# MotionBoard_Rev_B.net
KiCad netlist of a schematic drawn in EAGLE
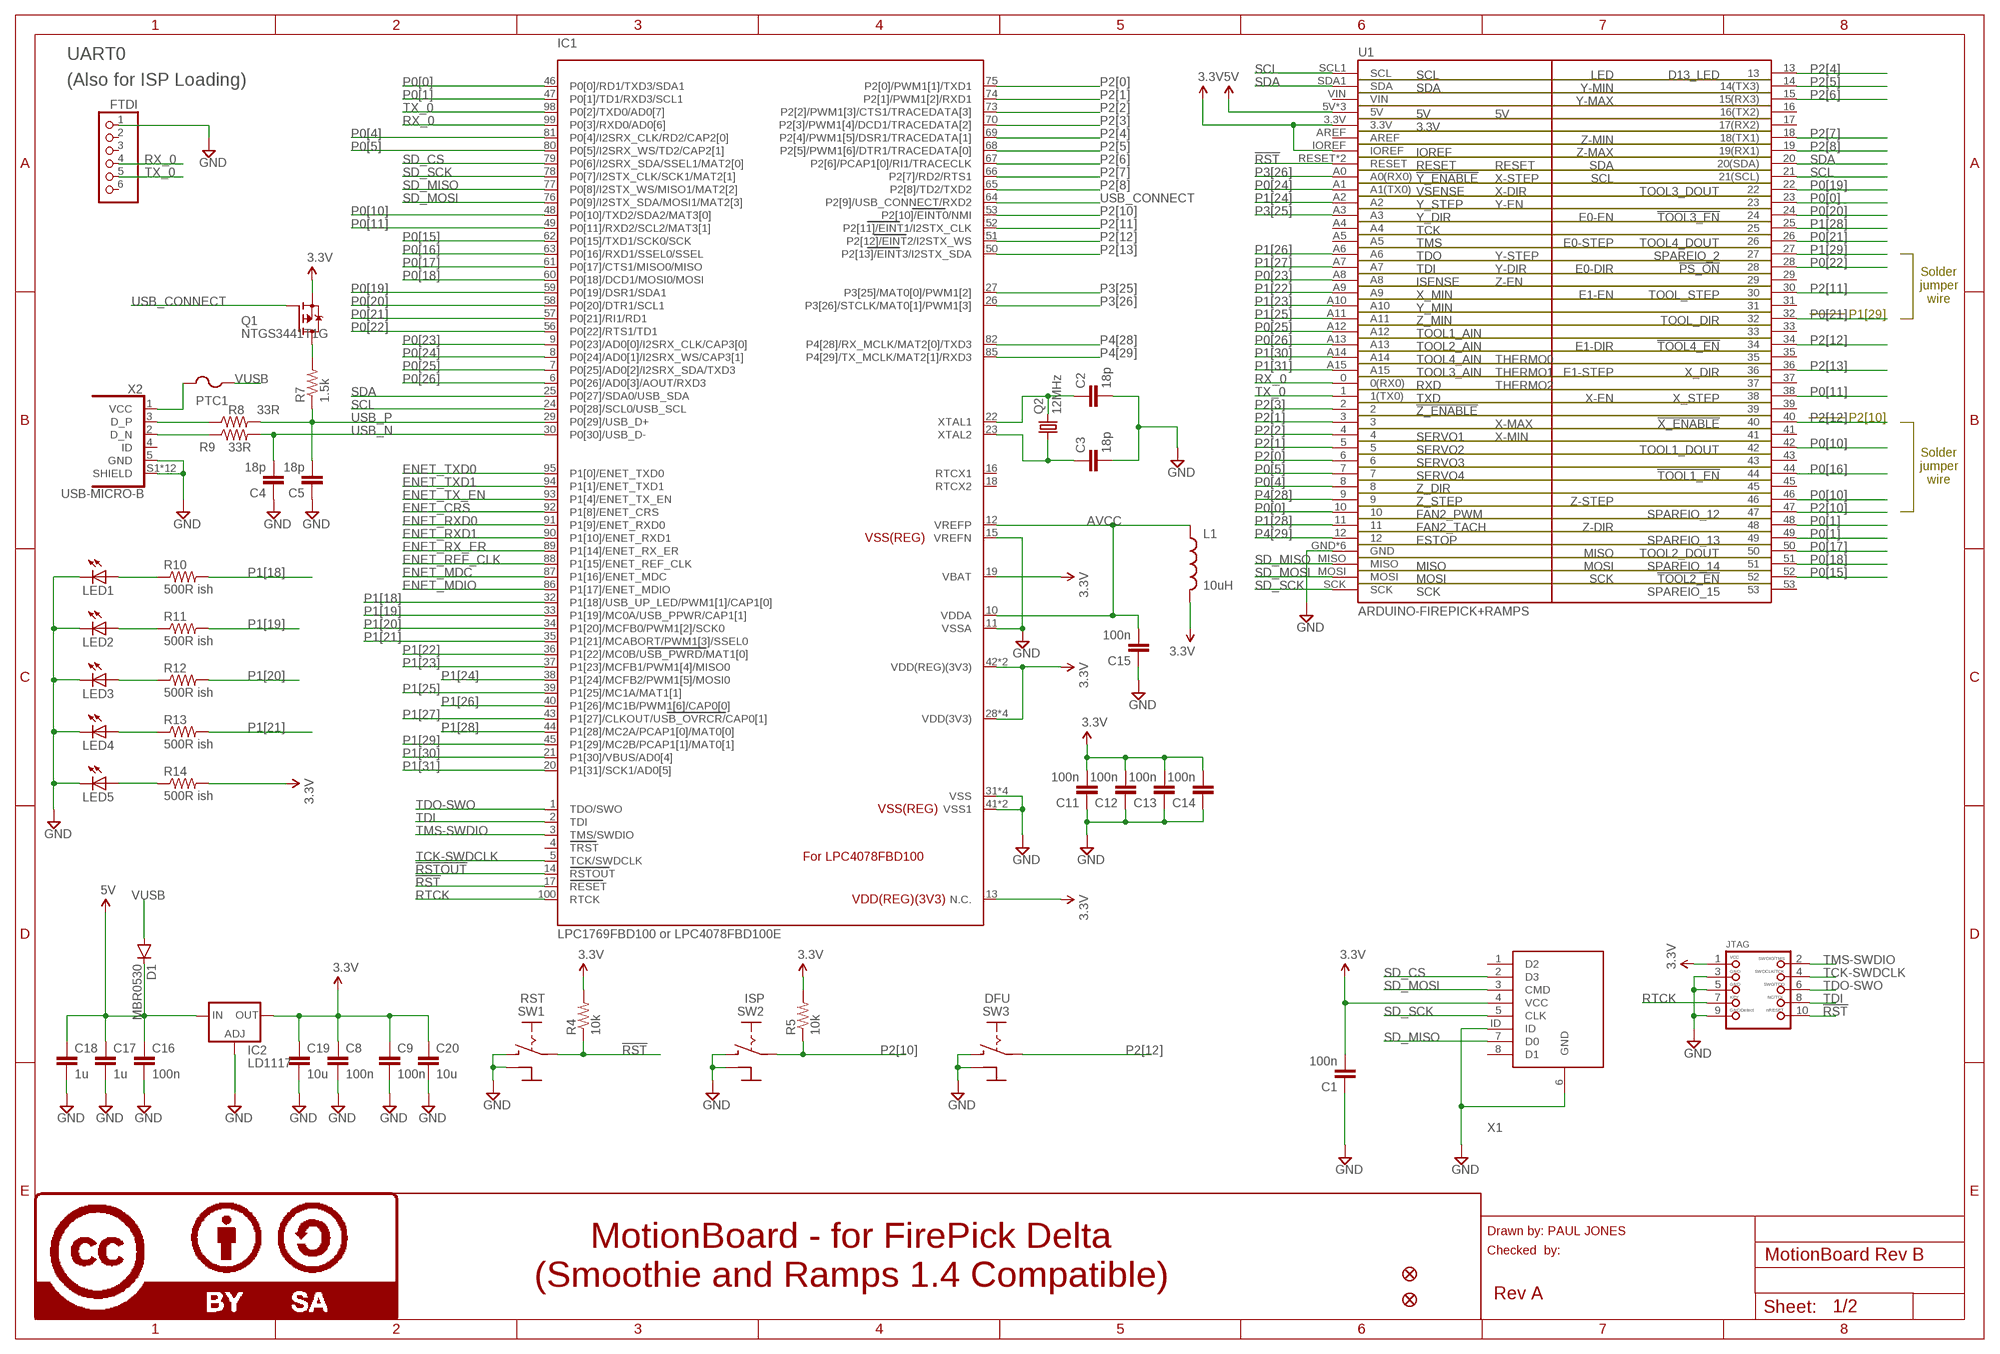
[diagram p0: schematic, sheet 1]
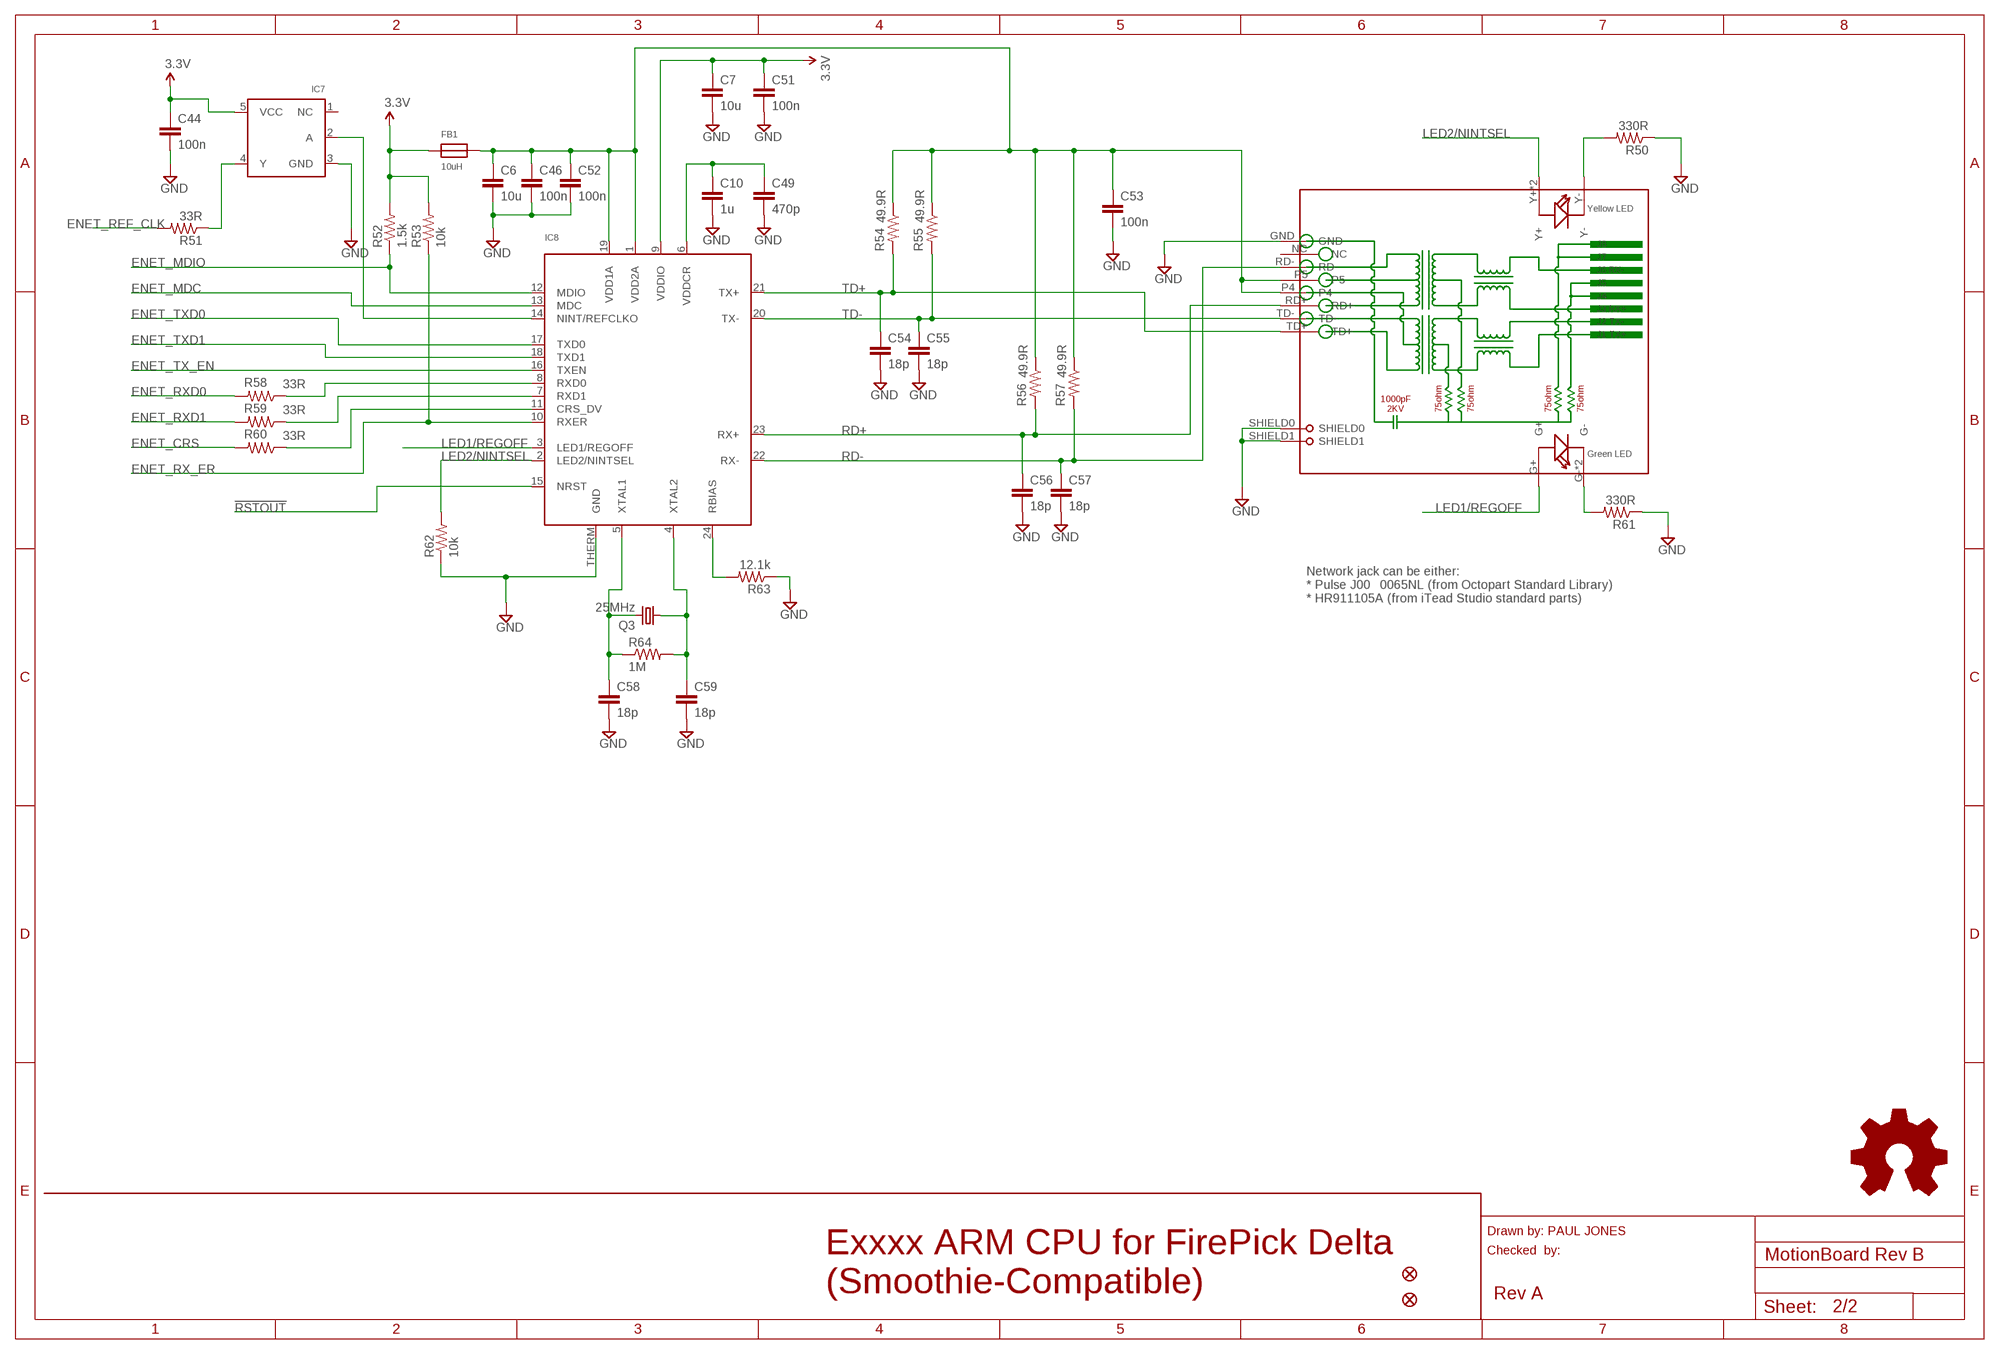
[diagram p1: schematic, sheet 2]

(export (version "E")
  (design (tool "Eeschema 10.0.6"))
  (components
    (comp (ref "C6")
      (value "10u")
      (footprint "eagle-import:0603")
      (libsource (lib "eagle-import") (part "CAP0603"))
    )
    (comp (ref "C7")
      (value "10u")
      (footprint "eagle-import:0603")
      (libsource (lib "eagle-import") (part "CAP0603"))
    )
    (comp (ref "C10")
      (value "1u")
      (footprint "eagle-import:0603")
      (libsource (lib "eagle-import") (part "CAP0603"))
    )
    (comp (ref "C44")
      (value "100n")
      (footprint "eagle-import:0603")
      (libsource (lib "eagle-import") (part "CAP0603"))
    )
    (comp (ref "C46")
      (value "100n")
      (footprint "eagle-import:0603")
      (libsource (lib "eagle-import") (part "CAP0603"))
    )
    (comp (ref "C49")
      (value "470p")
      (footprint "eagle-import:0603")
      (libsource (lib "eagle-import") (part "CAP0603"))
    )
    (comp (ref "C51")
      (value "100n")
      (footprint "eagle-import:0603")
      (libsource (lib "eagle-import") (part "CAP0603"))
    )
    (comp (ref "C52")
      (value "100n")
      (footprint "eagle-import:0603")
      (libsource (lib "eagle-import") (part "CAP0603"))
    )
    (comp (ref "C53")
      (value "100n")
      (footprint "eagle-import:0603")
      (libsource (lib "eagle-import") (part "CAP0603"))
    )
    (comp (ref "C54")
      (value "18p")
      (footprint "eagle-import:0603")
      (libsource (lib "eagle-import") (part "CAP0603"))
    )
    (comp (ref "C55")
      (value "18p")
      (footprint "eagle-import:0603")
      (libsource (lib "eagle-import") (part "CAP0603"))
    )
    (comp (ref "C56")
      (value "18p")
      (footprint "eagle-import:0603")
      (libsource (lib "eagle-import") (part "CAP0603"))
    )
    (comp (ref "C57")
      (value "18p")
      (footprint "eagle-import:0603")
      (libsource (lib "eagle-import") (part "CAP0603"))
    )
    (comp (ref "C58")
      (value "18p")
      (footprint "eagle-import:0603")
      (libsource (lib "eagle-import") (part "CAP0603"))
    )
    (comp (ref "C59")
      (value "18p")
      (footprint "eagle-import:0603")
      (libsource (lib "eagle-import") (part "CAP0603"))
    )
    (comp (ref "FB1")
      (value "10uH")
      (footprint "eagle-import:0603")
      (libsource (lib "eagle-import") (part "FERRITE"))
    )
    (comp (ref "FID17")
      (value "FIDUCIAL1X2")
      (footprint "eagle-import:FIDUCIAL-1X2")
      (libsource (lib "eagle-import") (part "FIDUCIAL1X2"))
    )
    (comp (ref "FID18")
      (value "FIDUCIAL1X2")
      (footprint "eagle-import:FIDUCIAL-1X2")
      (libsource (lib "eagle-import") (part "FIDUCIAL1X2"))
    )
    (comp (ref "IC7")
      (value "74LVC1G04")
      (footprint "eagle-import:SOT23-5")
      (libsource (lib "eagle-import") (part "74LVC1G04"))
    )
    (comp (ref "IC8")
      (value "LAN8720")
      (footprint "eagle-import:QFN24_4MM")
      (libsource (lib "eagle-import") (part "LAN8720"))
    )
    (comp (ref "LOGO10")
      (value "LOGO-OSHWSMALL")
      (footprint "eagle-import:LOGO-OSHW-SMALL")
      (libsource (lib "eagle-import") (part "LOGO-OSHWSMALL"))
    )
    (comp (ref "Q3")
      (value "25MHz")
      (footprint "eagle-import:HC49UP")
      (libsource (lib "eagle-import") (part "CRYSTALHC49UP"))
    )
    (comp (ref "R50")
      (value "330R")
      (footprint "eagle-import:R0603")
      (libsource (lib "eagle-import") (part "R-US_R0603"))
    )
    (comp (ref "R51")
      (value "33R")
      (footprint "eagle-import:R0603")
      (libsource (lib "eagle-import") (part "R-US_R0603"))
    )
    (comp (ref "R52")
      (value "1.5k")
      (footprint "eagle-import:R0603")
      (libsource (lib "eagle-import") (part "R-US_R0603"))
    )
    (comp (ref "R53")
      (value "10k")
      (footprint "eagle-import:R0603")
      (libsource (lib "eagle-import") (part "R-US_R0603"))
    )
    (comp (ref "R54")
      (value "49.9R")
      (footprint "eagle-import:R0603")
      (libsource (lib "eagle-import") (part "R-US_R0603"))
    )
    (comp (ref "R55")
      (value "49.9R")
      (footprint "eagle-import:R0603")
      (libsource (lib "eagle-import") (part "R-US_R0603"))
    )
    (comp (ref "R56")
      (value "49.9R")
      (footprint "eagle-import:R0603")
      (libsource (lib "eagle-import") (part "R-US_R0603"))
    )
    (comp (ref "R57")
      (value "49.9R")
      (footprint "eagle-import:R0603")
      (libsource (lib "eagle-import") (part "R-US_R0603"))
    )
    (comp (ref "R58")
      (value "33R")
      (footprint "eagle-import:R0603")
      (libsource (lib "eagle-import") (part "R-US_R0603"))
    )
    (comp (ref "R59")
      (value "33R")
      (footprint "eagle-import:R0603")
      (libsource (lib "eagle-import") (part "R-US_R0603"))
    )
    (comp (ref "R60")
      (value "33R")
      (footprint "eagle-import:R0603")
      (libsource (lib "eagle-import") (part "R-US_R0603"))
    )
    (comp (ref "R61")
      (value "330R")
      (footprint "eagle-import:R0603")
      (libsource (lib "eagle-import") (part "R-US_R0603"))
    )
    (comp (ref "R62")
      (value "10k")
      (footprint "eagle-import:R0603")
      (libsource (lib "eagle-import") (part "R-US_R0603"))
    )
    (comp (ref "R63")
      (value "12.1k")
      (footprint "eagle-import:R0603")
      (libsource (lib "eagle-import") (part "R-US_R0603"))
    )
    (comp (ref "R64")
      (value "1M")
      (footprint "eagle-import:R0603")
      (libsource (lib "eagle-import") (part "R-US_R0603"))
    )
    (comp (ref "RJ1")
      (value "HR911105A")
      (footprint "eagle-import:HR911105A")
      (libsource (lib "eagle-import") (part "HR911105A"))
    )
    (comp (ref "C1")
      (value "100n")
      (footprint "eagle-import:0603")
      (libsource (lib "eagle-import") (part "CAP0603"))
    )
    (comp (ref "C2")
      (value "18p")
      (footprint "eagle-import:0603")
      (libsource (lib "eagle-import") (part "CAP0603"))
    )
    (comp (ref "C3")
      (value "18p")
      (footprint "eagle-import:0603")
      (libsource (lib "eagle-import") (part "CAP0603"))
    )
    (comp (ref "C4")
      (value "18p")
      (footprint "eagle-import:0603")
      (libsource (lib "eagle-import") (part "CAP0603"))
    )
    (comp (ref "C5")
      (value "18p")
      (footprint "eagle-import:0603")
      (libsource (lib "eagle-import") (part "CAP0603"))
    )
    (comp (ref "C8")
      (value "100n")
      (footprint "eagle-import:0603")
      (libsource (lib "eagle-import") (part "CAP0603"))
    )
    (comp (ref "C9")
      (value "100n")
      (footprint "eagle-import:0603")
      (libsource (lib "eagle-import") (part "CAP0603"))
    )
    (comp (ref "C11")
      (value "100n")
      (footprint "eagle-import:0603")
      (libsource (lib "eagle-import") (part "CAP0603"))
    )
    (comp (ref "C12")
      (value "100n")
      (footprint "eagle-import:0603")
      (libsource (lib "eagle-import") (part "CAP0603"))
    )
    (comp (ref "C13")
      (value "100n")
      (footprint "eagle-import:0603")
      (libsource (lib "eagle-import") (part "CAP0603"))
    )
    (comp (ref "C14")
      (value "100n")
      (footprint "eagle-import:0603")
      (libsource (lib "eagle-import") (part "CAP0603"))
    )
    (comp (ref "C15")
      (value "100n")
      (footprint "eagle-import:0603")
      (libsource (lib "eagle-import") (part "CAP0603"))
    )
    (comp (ref "C16")
      (value "100n")
      (footprint "eagle-import:0603")
      (libsource (lib "eagle-import") (part "CAP0603"))
    )
    (comp (ref "C17")
      (value "1u")
      (footprint "eagle-import:0603")
      (libsource (lib "eagle-import") (part "CAP0603"))
    )
    (comp (ref "C18")
      (value "1u")
      (footprint "eagle-import:0603")
      (libsource (lib "eagle-import") (part "CAP0603"))
    )
    (comp (ref "C19")
      (value "10u")
      (footprint "eagle-import:0603")
      (libsource (lib "eagle-import") (part "CAP0603"))
    )
    (comp (ref "C20")
      (value "10u")
      (footprint "eagle-import:0603")
      (libsource (lib "eagle-import") (part "CAP0603"))
    )
    (comp (ref "D1")
      (value "MBR0530")
      (footprint "eagle-import:SOD-123")
      (libsource (lib "eagle-import") (part "DIODESOD123"))
    )
    (comp (ref "DFU")
      (value "SW3")
      (footprint "eagle-import:TOGGLE-SW-SMD")
      (libsource (lib "eagle-import") (part "TOGGLE-SW-SMD"))
    )
    (comp (ref "FID5")
      (value "FIDUCIAL1X2")
      (footprint "eagle-import:FIDUCIAL-1X2")
      (libsource (lib "eagle-import") (part "FIDUCIAL1X2"))
    )
    (comp (ref "FID6")
      (value "FIDUCIAL1X2")
      (footprint "eagle-import:FIDUCIAL-1X2")
      (libsource (lib "eagle-import") (part "FIDUCIAL1X2"))
    )
    (comp (ref "FTDI")
      (value "PINHD-1X6")
      (footprint "eagle-import:1X06")
      (libsource (lib "eagle-import") (part "PINHD-1X6"))
    )
    (comp (ref "IC1")
      (value "LPC1769FBD100 or LPC4078FBD100E")
      (footprint "eagle-import:LQFP100")
      (libsource (lib "eagle-import") (part "LPC1768"))
    )
    (comp (ref "IC2")
      (value "LD1117")
      (footprint "eagle-import:SOT223")
      (libsource (lib "eagle-import") (part "LD117A?S12TR"))
    )
    (comp (ref "ISP")
      (value "SW2")
      (footprint "eagle-import:TOGGLE-SW-SMD")
      (libsource (lib "eagle-import") (part "TOGGLE-SW-SMD"))
    )
    (comp (ref "JTAG")
      (value "JTAG-CORTEXM3")
      (footprint "eagle-import:2X05_1.27MM_SMT")
      (libsource (lib "eagle-import") (part "JTAG-CORTEXM3"))
    )
    (comp (ref "L1")
      (value "10uH")
      (footprint "eagle-import:0603")
      (libsource (lib "eagle-import") (part "INDUCTOR0603"))
    )
    (comp (ref "LED1")
      (value "LED")
      (footprint "eagle-import:LED-1206-BOTTOM")
      (libsource (lib "eagle-import") (part "LED"))
    )
    (comp (ref "LED2")
      (value "LED")
      (footprint "eagle-import:LED-1206-BOTTOM")
      (libsource (lib "eagle-import") (part "LED"))
    )
    (comp (ref "LED3")
      (value "LED")
      (footprint "eagle-import:LED-1206-BOTTOM")
      (libsource (lib "eagle-import") (part "LED"))
    )
    (comp (ref "LED4")
      (value "LED")
      (footprint "eagle-import:LED-1206-BOTTOM")
      (libsource (lib "eagle-import") (part "LED"))
    )
    (comp (ref "LED5")
      (value "LED")
      (footprint "eagle-import:LED-1206-BOTTOM")
      (libsource (lib "eagle-import") (part "LED"))
    )
    (comp (ref "LOGO6")
      (value "LOGO-CC-BY-SAMEDIUM")
      (footprint "eagle-import:LOGO-CC-BY-SA-MEDIUM")
      (libsource (lib "eagle-import") (part "LOGO-CC-BY-SAMEDIUM"))
    )
    (comp (ref "PTC1")
      (value "PTCFUSE-1812")
      (footprint "eagle-import:1812")
      (libsource (lib "eagle-import") (part "PTCFUSE-1812"))
    )
    (comp (ref "Q1")
      (value "NTGS3441T1G")
      (footprint "eagle-import:SC74_INFINEON")
      (libsource (lib "eagle-import") (part "BSL207SP"))
    )
    (comp (ref "Q2")
      (value "12MHz")
      (footprint "eagle-import:HC49UP")
      (libsource (lib "eagle-import") (part "CRYSTALHC49UP"))
    )
    (comp (ref "R4")
      (value "10k")
      (footprint "eagle-import:R0603")
      (libsource (lib "eagle-import") (part "R-US_R0603"))
    )
    (comp (ref "R5")
      (value "10k")
      (footprint "eagle-import:R0603")
      (libsource (lib "eagle-import") (part "R-US_R0603"))
    )
    (comp (ref "R7")
      (value "1.5k")
      (footprint "eagle-import:R0603")
      (libsource (lib "eagle-import") (part "R-US_R0603"))
    )
    (comp (ref "R8")
      (value "33R")
      (footprint "eagle-import:R0603")
      (libsource (lib "eagle-import") (part "R-US_R0603"))
    )
    (comp (ref "R9")
      (value "33R")
      (footprint "eagle-import:R0603")
      (libsource (lib "eagle-import") (part "R-US_R0603"))
    )
    (comp (ref "R10")
      (value "500R ish")
      (footprint "eagle-import:R0603")
      (libsource (lib "eagle-import") (part "R-US_R0603"))
    )
    (comp (ref "R11")
      (value "500R ish")
      (footprint "eagle-import:R0603")
      (libsource (lib "eagle-import") (part "R-US_R0603"))
    )
    (comp (ref "R12")
      (value "500R ish")
      (footprint "eagle-import:R0603")
      (libsource (lib "eagle-import") (part "R-US_R0603"))
    )
    (comp (ref "R13")
      (value "500R ish")
      (footprint "eagle-import:R0603")
      (libsource (lib "eagle-import") (part "R-US_R0603"))
    )
    (comp (ref "R14")
      (value "500R ish")
      (footprint "eagle-import:R0603")
      (libsource (lib "eagle-import") (part "R-US_R0603"))
    )
    (comp (ref "RST")
      (value "SW1")
      (footprint "eagle-import:TOGGLE-SW-SMD")
      (libsource (lib "eagle-import") (part "TOGGLE-SW-SMD"))
    )
    (comp (ref "U1")
      (value "ARDUINO-FIREPICK+RAMPS")
      (footprint "eagle-import:ARDUINO_MEGA_NEW")
      (libsource (lib "eagle-import") (part "ARDUINO-FIREPICK+RAMPS"))
    )
    (comp (ref "X1")
      (value "ST9S008V4AR1500")
      (footprint "eagle-import:ST9S008V4AR1500")
      (libsource (lib "eagle-import") (part "ST9S008V4AR1500"))
    )
    (comp (ref "X2")
      (value "USB-MICRO-B")
      (footprint "eagle-import:FCI-10118194-0001LF")
      (libsource (lib "eagle-import") (part "USB-MICRO-B"))
    )
  )
  (nets
    (net (code "1") (name "3.3V") (class "Default")
      (node (ref "C1") (pin "2") (pinfunction "2_2") (pintype "passive"))
      (node (ref "C11") (pin "2") (pinfunction "2_2") (pintype "passive"))
      (node (ref "C12") (pin "2") (pinfunction "2_2") (pintype "passive"))
      (node (ref "C13") (pin "2") (pinfunction "2_2") (pintype "passive"))
      (node (ref "C14") (pin "2") (pinfunction "2_2") (pintype "passive"))
      (node (ref "C19") (pin "1") (pinfunction "1_1") (pintype "passive"))
      (node (ref "C20") (pin "1") (pinfunction "1_1") (pintype "passive"))
      (node (ref "C44") (pin "1") (pinfunction "1_1") (pintype "passive"))
      (node (ref "C51") (pin "1") (pinfunction "1_1") (pintype "passive"))
      (node (ref "C7") (pin "1") (pinfunction "1_1") (pintype "passive"))
      (node (ref "C8") (pin "1") (pinfunction "1_1") (pintype "passive"))
      (node (ref "C9") (pin "1") (pinfunction "1_1") (pintype "passive"))
      (node (ref "FB1") (pin "1") (pinfunction "P$1_1") (pintype "bidirectional"))
      (node (ref "IC1") (pin "13") (pinfunction "N.C._13") (pintype "bidirectional"))
      (node (ref "IC1") (pin "19") (pinfunction "VBAT_19") (pintype "bidirectional"))
      (node (ref "IC1") (pin "28") (pinfunction "VDD(3V3)_28") (pintype "bidirectional"))
      (node (ref "IC1") (pin "42") (pinfunction "VDD(REG)(3V3)_42") (pintype "bidirectional"))
      (node (ref "IC1") (pin "54") (pinfunction "VDD(3V3)_54") (pintype "bidirectional"))
      (node (ref "IC1") (pin "71") (pinfunction "VDD(3V3)_71") (pintype "bidirectional"))
      (node (ref "IC1") (pin "84") (pinfunction "VDD(REG)(3V3)_84") (pintype "bidirectional"))
      (node (ref "IC1") (pin "96") (pinfunction "VDD(3V3)_96") (pintype "bidirectional"))
      (node (ref "IC2") (pin "4") (pinfunction "OUT_4") (pintype "passive"))
      (node (ref "IC7") (pin "5") (pinfunction "VCC_5") (pintype "power_in"))
      (node (ref "IC8") (pin "9") (pinfunction "VDDIO_9") (pintype "bidirectional"))
      (node (ref "JTAG") (pin "1") (pinfunction "1_1") (pintype "passive"))
      (node (ref "L1") (pin "2") (pinfunction "2_2") (pintype "passive"))
      (node (ref "Q1") (pin "4") (pinfunction "S_4") (pintype "passive"))
      (node (ref "R14") (pin "2") (pinfunction "2_2") (pintype "passive"))
      (node (ref "R4") (pin "2") (pinfunction "2_2") (pintype "passive"))
      (node (ref "R5") (pin "2") (pinfunction "2_2") (pintype "passive"))
      (node (ref "R52") (pin "2") (pinfunction "2_2") (pintype "passive"))
      (node (ref "R53") (pin "2") (pinfunction "2_2") (pintype "passive"))
      (node (ref "U1") (pin "3.3V") (pinfunction "3.3V_3.3V") (pintype "bidirectional"))
      (node (ref "U1") (pin "IOREF") (pinfunction "IOREF_IOREF") (pintype "bidirectional"))
      (node (ref "X1") (pin "4") (pinfunction "VCC_4") (pintype "input"))
    )
    (net (code "2") (name "5V") (class "Default")
      (node (ref "C16") (pin "1") (pinfunction "1_1") (pintype "passive"))
      (node (ref "C17") (pin "1") (pinfunction "1_1") (pintype "passive"))
      (node (ref "C18") (pin "1") (pinfunction "1_1") (pintype "passive"))
      (node (ref "D1") (pin "C") (pinfunction "C_C") (pintype "passive"))
      (node (ref "IC2") (pin "3") (pinfunction "IN_3") (pintype "input"))
      (node (ref "U1") (pin "5V") (pinfunction "5V_5V") (pintype "bidirectional"))
      (node (ref "U1") (pin "5V@1") (pinfunction "5V_5V@1") (pintype "bidirectional"))
      (node (ref "U1") (pin "5V@2") (pinfunction "5V_5V@2") (pintype "bidirectional"))
    )
    (net (code "3") (name "AVCC") (class "Default")
      (node (ref "C15") (pin "2") (pinfunction "2_2") (pintype "passive"))
      (node (ref "IC1") (pin "10") (pinfunction "VDDA_10") (pintype "bidirectional"))
      (node (ref "IC1") (pin "12") (pinfunction "VREFP_12") (pintype "bidirectional"))
      (node (ref "L1") (pin "1") (pinfunction "1_1") (pintype "passive"))
    )
    (net (code "4") (name "ENET_CRS") (class "Default")
      (node (ref "IC1") (pin "92") (pinfunction "P1[8]/ENET_CRS_92") (pintype "bidirectional"))
      (node (ref "R60") (pin "2") (pinfunction "2_2") (pintype "passive"))
    )
    (net (code "5") (name "ENET_MDC") (class "Default")
      (node (ref "IC1") (pin "87") (pinfunction "P1[16]/ENET_MDC_87") (pintype "bidirectional"))
      (node (ref "IC8") (pin "13") (pinfunction "MDC_13") (pintype "bidirectional"))
    )
    (net (code "6") (name "ENET_MDIO") (class "Default")
      (node (ref "IC1") (pin "86") (pinfunction "P1[17]/ENET_MDIO_86") (pintype "bidirectional"))
      (node (ref "IC8") (pin "12") (pinfunction "MDIO_12") (pintype "bidirectional"))
      (node (ref "R52") (pin "1") (pinfunction "1_1") (pintype "passive"))
    )
    (net (code "7") (name "ENET_REF_CLK") (class "Default")
      (node (ref "IC1") (pin "88") (pinfunction "P1[15]/ENET_REF_CLK_88") (pintype "bidirectional"))
      (node (ref "R51") (pin "2") (pinfunction "2_2") (pintype "passive"))
    )
    (net (code "8") (name "ENET_RXD0") (class "Default")
      (node (ref "IC1") (pin "91") (pinfunction "P1[9]/ENET_RXD0_91") (pintype "bidirectional"))
      (node (ref "R58") (pin "2") (pinfunction "2_2") (pintype "passive"))
    )
    (net (code "9") (name "ENET_RXD1") (class "Default")
      (node (ref "IC1") (pin "90") (pinfunction "P1[10]/ENET_RXD1_90") (pintype "bidirectional"))
      (node (ref "R59") (pin "2") (pinfunction "2_2") (pintype "passive"))
    )
    (net (code "10") (name "ENET_RX_ER") (class "Default")
      (node (ref "IC1") (pin "89") (pinfunction "P1[14]/ENET_RX_ER_89") (pintype "bidirectional"))
      (node (ref "IC8") (pin "10") (pinfunction "RXER_10") (pintype "bidirectional"))
      (node (ref "R53") (pin "1") (pinfunction "1_1") (pintype "passive"))
    )
    (net (code "11") (name "ENET_TXD0") (class "Default")
      (node (ref "IC1") (pin "95") (pinfunction "P1[0]/ENET_TXD0_95") (pintype "bidirectional"))
      (node (ref "IC8") (pin "17") (pinfunction "TXD0_17") (pintype "bidirectional"))
    )
    (net (code "12") (name "ENET_TXD1") (class "Default")
      (node (ref "IC1") (pin "94") (pinfunction "P1[1]/ENET_TXD1_94") (pintype "bidirectional"))
      (node (ref "IC8") (pin "18") (pinfunction "TXD1_18") (pintype "bidirectional"))
    )
    (net (code "13") (name "ENET_TX_EN") (class "Default")
      (node (ref "IC1") (pin "93") (pinfunction "P1[4]/ENET_TX_EN_93") (pintype "bidirectional"))
      (node (ref "IC8") (pin "16") (pinfunction "TXEN_16") (pintype "bidirectional"))
    )
    (net (code "14") (name "GND") (class "Default")
      (node (ref "C1") (pin "1") (pinfunction "1_1") (pintype "passive"))
      (node (ref "C10") (pin "2") (pinfunction "2_2") (pintype "passive"))
      (node (ref "C11") (pin "1") (pinfunction "1_1") (pintype "passive"))
      (node (ref "C12") (pin "1") (pinfunction "1_1") (pintype "passive"))
      (node (ref "C13") (pin "1") (pinfunction "1_1") (pintype "passive"))
      (node (ref "C14") (pin "1") (pinfunction "1_1") (pintype "passive"))
      (node (ref "C15") (pin "1") (pinfunction "1_1") (pintype "passive"))
      (node (ref "C16") (pin "2") (pinfunction "2_2") (pintype "passive"))
      (node (ref "C17") (pin "2") (pinfunction "2_2") (pintype "passive"))
      (node (ref "C18") (pin "2") (pinfunction "2_2") (pintype "passive"))
      (node (ref "C19") (pin "2") (pinfunction "2_2") (pintype "passive"))
      (node (ref "C2") (pin "2") (pinfunction "2_2") (pintype "passive"))
      (node (ref "C20") (pin "2") (pinfunction "2_2") (pintype "passive"))
      (node (ref "C3") (pin "2") (pinfunction "2_2") (pintype "passive"))
      (node (ref "C4") (pin "1") (pinfunction "1_1") (pintype "passive"))
      (node (ref "C44") (pin "2") (pinfunction "2_2") (pintype "passive"))
      (node (ref "C46") (pin "2") (pinfunction "2_2") (pintype "passive"))
      (node (ref "C49") (pin "2") (pinfunction "2_2") (pintype "passive"))
      (node (ref "C5") (pin "1") (pinfunction "1_1") (pintype "passive"))
      (node (ref "C51") (pin "2") (pinfunction "2_2") (pintype "passive"))
      (node (ref "C52") (pin "2") (pinfunction "2_2") (pintype "passive"))
      (node (ref "C53") (pin "2") (pinfunction "2_2") (pintype "passive"))
      (node (ref "C54") (pin "2") (pinfunction "2_2") (pintype "passive"))
      (node (ref "C55") (pin "2") (pinfunction "2_2") (pintype "passive"))
      (node (ref "C56") (pin "2") (pinfunction "2_2") (pintype "passive"))
      (node (ref "C57") (pin "2") (pinfunction "2_2") (pintype "passive"))
      (node (ref "C58") (pin "2") (pinfunction "2_2") (pintype "passive"))
      (node (ref "C59") (pin "2") (pinfunction "2_2") (pintype "passive"))
      (node (ref "C6") (pin "2") (pinfunction "2_2") (pintype "passive"))
      (node (ref "C7") (pin "2") (pinfunction "2_2") (pintype "passive"))
      (node (ref "C8") (pin "2") (pinfunction "2_2") (pintype "passive"))
      (node (ref "C9") (pin "2") (pinfunction "2_2") (pintype "passive"))
      (node (ref "DFU") (pin "1") (pinfunction "C_1") (pintype "passive"))
      (node (ref "DFU") (pin "2") (pinfunction "C_2") (pintype "passive"))
      (node (ref "DFU") (pin "GND") (pinfunction "GND_GND") (pintype "passive"))
      (node (ref "FTDI") (pin "1") (pinfunction "1_1") (pintype "passive"))
      (node (ref "IC1") (pin "11") (pinfunction "VSSA_11") (pintype "bidirectional"))
      (node (ref "IC1") (pin "15") (pinfunction "VREFN_15") (pintype "bidirectional"))
      (node (ref "IC1") (pin "31") (pinfunction "VSS_31") (pintype "bidirectional"))
      (node (ref "IC1") (pin "41") (pinfunction "VSS1_41") (pintype "bidirectional"))
      (node (ref "IC1") (pin "55") (pinfunction "VSS_55") (pintype "bidirectional"))
      (node (ref "IC1") (pin "72") (pinfunction "VSS_72") (pintype "bidirectional"))
      (node (ref "IC1") (pin "83") (pinfunction "VSS1_83") (pintype "bidirectional"))
      (node (ref "IC1") (pin "97") (pinfunction "VSS_97") (pintype "bidirectional"))
      (node (ref "IC2") (pin "1") (pinfunction "ADJ_1") (pintype "input"))
      (node (ref "IC7") (pin "3") (pinfunction "GND_3") (pintype "power_in"))
      (node (ref "IC8") (pin "THERM") (pinfunction "GND_THERM") (pintype "bidirectional"))
      (node (ref "ISP") (pin "1") (pinfunction "C_1") (pintype "passive"))
      (node (ref "ISP") (pin "2") (pinfunction "C_2") (pintype "passive"))
      (node (ref "ISP") (pin "GND") (pinfunction "GND_GND") (pintype "passive"))
      (node (ref "JTAG") (pin "3") (pinfunction "3_3") (pintype "passive"))
      (node (ref "JTAG") (pin "5") (pinfunction "5_5") (pintype "passive"))
      (node (ref "JTAG") (pin "9") (pinfunction "9_9") (pintype "passive"))
      (node (ref "LED1") (pin "C") (pinfunction "C_C") (pintype "passive"))
      (node (ref "LED2") (pin "C") (pinfunction "C_C") (pintype "passive"))
      (node (ref "LED3") (pin "C") (pinfunction "C_C") (pintype "passive"))
      (node (ref "LED4") (pin "C") (pinfunction "C_C") (pintype "passive"))
      (node (ref "LED5") (pin "C") (pinfunction "C_C") (pintype "passive"))
      (node (ref "R50") (pin "1") (pinfunction "1_1") (pintype "passive"))
      (node (ref "R61") (pin "1") (pinfunction "1_1") (pintype "passive"))
      (node (ref "R62") (pin "1") (pinfunction "1_1") (pintype "passive"))
      (node (ref "R63") (pin "1") (pinfunction "1_1") (pintype "passive"))
      (node (ref "RJ1") (pin "GND") (pinfunction "GND_GND") (pintype "bidirectional"))
      (node (ref "RJ1") (pin "SHIELD0") (pinfunction "SHIELD0_SHIELD0") (pintype "bidirectional"))
      (node (ref "RJ1") (pin "SHIELD1") (pinfunction "SHIELD1_SHIELD1") (pintype "bidirectional"))
      (node (ref "RST") (pin "1") (pinfunction "C_1") (pintype "passive"))
      (node (ref "RST") (pin "2") (pinfunction "C_2") (pintype "passive"))
      (node (ref "RST") (pin "GND") (pinfunction "GND_GND") (pintype "passive"))
      (node (ref "U1") (pin "GND") (pinfunction "GND_GND") (pintype "bidirectional"))
      (node (ref "U1") (pin "GND@0") (pinfunction "GND_GND@0") (pintype "bidirectional"))
      (node (ref "U1") (pin "GND@1") (pinfunction "GND_GND@1") (pintype "bidirectional"))
      (node (ref "U1") (pin "GND@2") (pinfunction "GND_GND@2") (pintype "bidirectional"))
      (node (ref "U1") (pin "GND@3") (pinfunction "GND_GND@3") (pintype "bidirectional"))
      (node (ref "U1") (pin "GNDI") (pinfunction "GND_GNDI") (pintype "bidirectional"))
      (node (ref "X1") (pin "6") (pinfunction "GND_6") (pintype "passive"))
      (node (ref "X1") (pin "ID") (pinfunction "ID_ID") (pintype "passive"))
      (node (ref "X2") (pin "5") (pinfunction "GND_5") (pintype "bidirectional"))
      (node (ref "X2") (pin "S1") (pinfunction "SHIELD_S1") (pintype "bidirectional"))
      (node (ref "X2") (pin "S10") (pinfunction "SHIELD_S10") (pintype "bidirectional"))
      (node (ref "X2") (pin "S11") (pinfunction "SHIELD_S11") (pintype "bidirectional"))
      (node (ref "X2") (pin "S12") (pinfunction "SHIELD_S12") (pintype "bidirectional"))
      (node (ref "X2") (pin "S2") (pinfunction "SHIELD_S2") (pintype "bidirectional"))
      (node (ref "X2") (pin "S3") (pinfunction "SHIELD_S3") (pintype "bidirectional"))
      (node (ref "X2") (pin "S4") (pinfunction "SHIELD_S4") (pintype "bidirectional"))
      (node (ref "X2") (pin "S5") (pinfunction "SHIELD_S5") (pintype "bidirectional"))
      (node (ref "X2") (pin "S6") (pinfunction "SHIELD_S6") (pintype "bidirectional"))
      (node (ref "X2") (pin "S7") (pinfunction "SHIELD_S7") (pintype "bidirectional"))
      (node (ref "X2") (pin "S8") (pinfunction "SHIELD_S8") (pintype "bidirectional"))
      (node (ref "X2") (pin "S9") (pinfunction "SHIELD_S9") (pintype "bidirectional"))
    )
    (net (code "15") (name "LED1{slash}REGOFF") (class "Default")
      (node (ref "IC8") (pin "3") (pinfunction "LED1/REGOFF_3") (pintype "bidirectional"))
      (node (ref "RJ1") (pin "G+") (pinfunction "G+_G+") (pintype "bidirectional"))
    )
    (net (code "16") (name "LED2{slash}NINTSEL") (class "Default")
      (node (ref "IC8") (pin "2") (pinfunction "LED2/NINTSEL_2") (pintype "bidirectional"))
      (node (ref "R62") (pin "2") (pinfunction "2_2") (pintype "passive"))
      (node (ref "RJ1") (pin "Y+") (pinfunction "Y+_Y+") (pintype "bidirectional"))
      (node (ref "RJ1") (pin "Y++") (pinfunction "Y+_Y++") (pintype "bidirectional"))
    )
    (net (code "17") (name "Net-(FB1-P$2)") (class "Default")
      (node (ref "C46") (pin "1") (pinfunction "1_1") (pintype "passive"))
      (node (ref "C52") (pin "1") (pinfunction "1_1") (pintype "passive"))
      (node (ref "C53") (pin "1") (pinfunction "1_1") (pintype "passive"))
      (node (ref "C6") (pin "1") (pinfunction "1_1") (pintype "passive"))
      (node (ref "FB1") (pin "2") (pinfunction "P$2_2") (pintype "bidirectional"))
      (node (ref "IC8") (pin "1") (pinfunction "VDD2A_1") (pintype "bidirectional"))
      (node (ref "IC8") (pin "19") (pinfunction "VDD1A_19") (pintype "bidirectional"))
      (node (ref "R54") (pin "1") (pinfunction "1_1") (pintype "passive"))
      (node (ref "R55") (pin "1") (pinfunction "1_1") (pintype "passive"))
      (node (ref "R56") (pin "1") (pinfunction "1_1") (pintype "passive"))
      (node (ref "R57") (pin "1") (pinfunction "1_1") (pintype "passive"))
      (node (ref "RJ1") (pin "P4") (pinfunction "P4_P4") (pintype "bidirectional"))
      (node (ref "RJ1") (pin "P5") (pinfunction "P5_P5") (pintype "bidirectional"))
    )
    (net (code "18") (name "Net-(IC1-XTAL1)") (class "Default")
      (node (ref "C2") (pin "1") (pinfunction "1_1") (pintype "passive"))
      (node (ref "IC1") (pin "22") (pinfunction "XTAL1_22") (pintype "bidirectional"))
      (node (ref "Q2") (pin "2") (pinfunction "2_2") (pintype "passive"))
    )
    (net (code "19") (name "Net-(IC1-XTAL2)") (class "Default")
      (node (ref "C3") (pin "1") (pinfunction "1_1") (pintype "passive"))
      (node (ref "IC1") (pin "23") (pinfunction "XTAL2_23") (pintype "bidirectional"))
      (node (ref "Q2") (pin "1") (pinfunction "1_1") (pintype "passive"))
    )
    (net (code "20") (name "Net-(IC7-A)") (class "Default")
      (node (ref "IC7") (pin "2") (pinfunction "A_2") (pintype "bidirectional"))
      (node (ref "IC8") (pin "14") (pinfunction "NINT/REFCLKO_14") (pintype "bidirectional"))
    )
    (net (code "21") (name "Net-(IC7-Y)") (class "Default")
      (node (ref "IC7") (pin "4") (pinfunction "Y_4") (pintype "bidirectional"))
      (node (ref "R51") (pin "1") (pinfunction "1_1") (pintype "passive"))
    )
    (net (code "22") (name "Net-(IC8-CRS_DV)") (class "Default")
      (node (ref "IC8") (pin "11") (pinfunction "CRS_DV_11") (pintype "bidirectional"))
      (node (ref "R60") (pin "1") (pinfunction "1_1") (pintype "passive"))
    )
    (net (code "23") (name "Net-(IC8-RBIAS)") (class "Default")
      (node (ref "IC8") (pin "24") (pinfunction "RBIAS_24") (pintype "bidirectional"))
      (node (ref "R63") (pin "2") (pinfunction "2_2") (pintype "passive"))
    )
    (net (code "24") (name "Net-(IC8-RXD0)") (class "Default")
      (node (ref "IC8") (pin "8") (pinfunction "RXD0_8") (pintype "bidirectional"))
      (node (ref "R58") (pin "1") (pinfunction "1_1") (pintype "passive"))
    )
    (net (code "25") (name "Net-(IC8-RXD1)") (class "Default")
      (node (ref "IC8") (pin "7") (pinfunction "RXD1_7") (pintype "bidirectional"))
      (node (ref "R59") (pin "1") (pinfunction "1_1") (pintype "passive"))
    )
    (net (code "26") (name "Net-(IC8-VDDCR)") (class "Default")
      (node (ref "C10") (pin "1") (pinfunction "1_1") (pintype "passive"))
      (node (ref "C49") (pin "1") (pinfunction "1_1") (pintype "passive"))
      (node (ref "IC8") (pin "6") (pinfunction "VDDCR_6") (pintype "bidirectional"))
    )
    (net (code "27") (name "Net-(IC8-XTAL1)") (class "Default")
      (node (ref "C58") (pin "1") (pinfunction "1_1") (pintype "passive"))
      (node (ref "IC8") (pin "5") (pinfunction "XTAL1_5") (pintype "bidirectional"))
      (node (ref "Q3") (pin "2") (pinfunction "2_2") (pintype "passive"))
      (node (ref "R64") (pin "1") (pinfunction "1_1") (pintype "passive"))
    )
    (net (code "28") (name "Net-(IC8-XTAL2)") (class "Default")
      (node (ref "C59") (pin "1") (pinfunction "1_1") (pintype "passive"))
      (node (ref "IC8") (pin "4") (pinfunction "XTAL2_4") (pintype "bidirectional"))
      (node (ref "Q3") (pin "1") (pinfunction "1_1") (pintype "passive"))
      (node (ref "R64") (pin "2") (pinfunction "2_2") (pintype "passive"))
    )
    (net (code "29") (name "Net-(LED1-PadA)") (class "Default")
      (node (ref "LED1") (pin "A") (pinfunction "A_A") (pintype "passive"))
      (node (ref "R10") (pin "1") (pinfunction "1_1") (pintype "passive"))
    )
    (net (code "30") (name "Net-(LED2-PadA)") (class "Default")
      (node (ref "LED2") (pin "A") (pinfunction "A_A") (pintype "passive"))
      (node (ref "R11") (pin "1") (pinfunction "1_1") (pintype "passive"))
    )
    (net (code "31") (name "Net-(LED3-PadA)") (class "Default")
      (node (ref "LED3") (pin "A") (pinfunction "A_A") (pintype "passive"))
      (node (ref "R12") (pin "1") (pinfunction "1_1") (pintype "passive"))
    )
    (net (code "32") (name "Net-(LED4-PadA)") (class "Default")
      (node (ref "LED4") (pin "A") (pinfunction "A_A") (pintype "passive"))
      (node (ref "R13") (pin "1") (pinfunction "1_1") (pintype "passive"))
    )
    (net (code "33") (name "Net-(LED5-PadA)") (class "Default")
      (node (ref "LED5") (pin "A") (pinfunction "A_A") (pintype "passive"))
      (node (ref "R14") (pin "1") (pinfunction "1_1") (pintype "passive"))
    )
    (net (code "34") (name "Net-(Q1-D-Pad1)") (class "Default")
      (node (ref "Q1") (pin "1") (pinfunction "D_1") (pintype "passive"))
      (node (ref "Q1") (pin "2") (pinfunction "D_2") (pintype "passive"))
      (node (ref "Q1") (pin "5") (pinfunction "D_5") (pintype "passive"))
      (node (ref "Q1") (pin "6") (pinfunction "D_6") (pintype "passive"))
      (node (ref "R7") (pin "2") (pinfunction "2_2") (pintype "passive"))
    )
    (net (code "35") (name "Net-(R50-Pad2)") (class "Default")
      (node (ref "R50") (pin "2") (pinfunction "2_2") (pintype "passive"))
      (node (ref "RJ1") (pin "Y-") (pinfunction "Y-_Y-") (pintype "bidirectional"))
    )
    (net (code "36") (name "Net-(R61-Pad2)") (class "Default")
      (node (ref "R61") (pin "2") (pinfunction "2_2") (pintype "passive"))
      (node (ref "RJ1") (pin "G-") (pinfunction "G-_G-") (pintype "bidirectional"))
      (node (ref "RJ1") (pin "G--") (pinfunction "G-_G--") (pintype "bidirectional"))
    )
    (net (code "37") (name "Net-(X2-D_N)") (class "Default")
      (node (ref "R9") (pin "1") (pinfunction "1_1") (pintype "passive"))
      (node (ref "X2") (pin "2") (pinfunction "D_N_2") (pintype "bidirectional"))
    )
    (net (code "38") (name "Net-(X2-D_P)") (class "Default")
      (node (ref "R8") (pin "1") (pinfunction "1_1") (pintype "passive"))
      (node (ref "X2") (pin "3") (pinfunction "D_P_3") (pintype "bidirectional"))
    )
    (net (code "39") (name "Net-(X2-VCC)") (class "Default")
      (node (ref "PTC1") (pin "2") (pinfunction "2_2") (pintype "passive"))
      (node (ref "X2") (pin "1") (pinfunction "VCC_1") (pintype "bidirectional"))
    )
    (net (code "40") (name "P0[0]") (class "Default")
      (node (ref "IC1") (pin "46") (pinfunction "P0[0]/RD1/TXD3/SDA1_46") (pintype "bidirectional"))
      (node (ref "U1") (pin "10") (pinfunction "10_10") (pintype "bidirectional"))
      (node (ref "U1") (pin "23") (pinfunction "23_23") (pintype "bidirectional"))
    )
    (net (code "41") (name "P0[1]") (class "Default")
      (node (ref "IC1") (pin "47") (pinfunction "P0[1]/TD1/RXD3/SCL1_47") (pintype "bidirectional"))
      (node (ref "U1") (pin "48") (pinfunction "48_48") (pintype "bidirectional"))
      (node (ref "U1") (pin "49") (pinfunction "49_49") (pintype "bidirectional"))
    )
    (net (code "42") (name "P0[4]") (class "Default")
      (node (ref "IC1") (pin "81") (pinfunction "P0[4]/I2SRX_CLK/RD2/CAP2[0]_81") (pintype "bidirectional"))
      (node (ref "U1") (pin "8") (pinfunction "8_8") (pintype "bidirectional"))
    )
    (net (code "43") (name "P0[5]") (class "Default")
      (node (ref "IC1") (pin "80") (pinfunction "P0[5]/I2SRX_WS/TD2/CAP2[1]_80") (pintype "bidirectional"))
      (node (ref "U1") (pin "7") (pinfunction "7_7") (pintype "bidirectional"))
    )
    (net (code "44") (name "P0[10]") (class "Default")
      (node (ref "IC1") (pin "48") (pinfunction "P0[10]/TXD2/SDA2/MAT3[0]_48") (pintype "bidirectional"))
      (node (ref "U1") (pin "42") (pinfunction "42_42") (pintype "bidirectional"))
      (node (ref "U1") (pin "46") (pinfunction "46_46") (pintype "bidirectional"))
    )
    (net (code "45") (name "P0[11]") (class "Default")
      (node (ref "IC1") (pin "49") (pinfunction "P0[11]/RXD2/SCL2/MAT3[1]_49") (pintype "bidirectional"))
      (node (ref "U1") (pin "38") (pinfunction "38_38") (pintype "bidirectional"))
    )
    (net (code "46") (name "P0[15]") (class "Default")
      (node (ref "IC1") (pin "62") (pinfunction "P0[15]/TXD1/SCK0/SCK_62") (pintype "bidirectional"))
      (node (ref "U1") (pin "52") (pinfunction "52_52") (pintype "bidirectional"))
    )
    (net (code "47") (name "P0[16]") (class "Default")
      (node (ref "IC1") (pin "63") (pinfunction "P0[16]/RXD1/SSEL0/SSEL_63") (pintype "bidirectional"))
      (node (ref "U1") (pin "44") (pinfunction "44_44") (pintype "bidirectional"))
    )
    (net (code "48") (name "P0[17]") (class "Default")
      (node (ref "IC1") (pin "61") (pinfunction "P0[17]/CTS1/MISO0/MISO_61") (pintype "bidirectional"))
      (node (ref "U1") (pin "50") (pinfunction "50_50") (pintype "bidirectional"))
    )
    (net (code "49") (name "P0[18]") (class "Default")
      (node (ref "IC1") (pin "60") (pinfunction "P0[18]/DCD1/MOSI0/MOSI_60") (pintype "bidirectional"))
      (node (ref "U1") (pin "51") (pinfunction "51_51") (pintype "bidirectional"))
    )
    (net (code "50") (name "P0[19]") (class "Default")
      (node (ref "IC1") (pin "59") (pinfunction "P0[19]/DSR1/SDA1_59") (pintype "bidirectional"))
      (node (ref "U1") (pin "22") (pinfunction "22_22") (pintype "bidirectional"))
    )
    (net (code "51") (name "P0[20]") (class "Default")
      (node (ref "IC1") (pin "58") (pinfunction "P0[20]/DTR1/SCL1_58") (pintype "bidirectional"))
      (node (ref "U1") (pin "24") (pinfunction "24_24") (pintype "bidirectional"))
    )
    (net (code "52") (name "P0[21]") (class "Default")
      (node (ref "IC1") (pin "57") (pinfunction "P0[21]/RI1/RD1_57") (pintype "bidirectional"))
      (node (ref "U1") (pin "26") (pinfunction "26_26") (pintype "bidirectional"))
      (node (ref "U1") (pin "32") (pinfunction "32_32") (pintype "bidirectional"))
    )
    (net (code "53") (name "P0[22]") (class "Default")
      (node (ref "IC1") (pin "56") (pinfunction "P0[22]/RTS1/TD1_56") (pintype "bidirectional"))
      (node (ref "U1") (pin "28") (pinfunction "28_28") (pintype "bidirectional"))
    )
    (net (code "54") (name "P0[23]") (class "Default")
      (node (ref "IC1") (pin "9") (pinfunction "P0[23]/AD0[0]/I2SRX_CLK/CAP3[0]_9") (pintype "bidirectional"))
      (node (ref "U1") (pin "A8") (pinfunction "A8_A8") (pintype "bidirectional"))
    )
    (net (code "55") (name "P0[24]") (class "Default")
      (node (ref "IC1") (pin "8") (pinfunction "P0[24]/AD0[1]/I2SRX_WS/CAP3[1]_8") (pintype "bidirectional"))
      (node (ref "U1") (pin "A1") (pinfunction "A1(TX0)_A1") (pintype "bidirectional"))
    )
    (net (code "56") (name "P0[25]") (class "Default")
      (node (ref "IC1") (pin "7") (pinfunction "P0[25]/AD0[2]/I2SRX_SDA/TXD3_7") (pintype "bidirectional"))
      (node (ref "U1") (pin "A12") (pinfunction "A12_A12") (pintype "bidirectional"))
    )
    (net (code "57") (name "P0[26]") (class "Default")
      (node (ref "IC1") (pin "6") (pinfunction "P0[26]/AD0[3]/AOUT/RXD3_6") (pintype "bidirectional"))
      (node (ref "U1") (pin "A13") (pinfunction "A13_A13") (pintype "bidirectional"))
    )
    (net (code "58") (name "P1[18]") (class "Default")
      (node (ref "IC1") (pin "32") (pinfunction "P1[18]/USB_UP_LED/PWM1[1]/CAP1[0]_32") (pintype "bidirectional"))
      (node (ref "R10") (pin "2") (pinfunction "2_2") (pintype "passive"))
    )
    (net (code "59") (name "P1[19]") (class "Default")
      (node (ref "IC1") (pin "33") (pinfunction "P1[19]/MC0A/USB_PPWR/CAP1[1]_33") (pintype "bidirectional"))
      (node (ref "R11") (pin "2") (pinfunction "2_2") (pintype "passive"))
    )
    (net (code "60") (name "P1[20]") (class "Default")
      (node (ref "IC1") (pin "34") (pinfunction "P1[20]/MCFB0/PWM1[2]/SCK0_34") (pintype "bidirectional"))
      (node (ref "R12") (pin "2") (pinfunction "2_2") (pintype "passive"))
    )
    (net (code "61") (name "P1[21]") (class "Default")
      (node (ref "IC1") (pin "35") (pinfunction "P1[21]/MCABORT/PWM1[3]/SSEL0_35") (pintype "bidirectional"))
      (node (ref "R13") (pin "2") (pinfunction "2_2") (pintype "passive"))
    )
    (net (code "62") (name "P1[22]") (class "Default")
      (node (ref "IC1") (pin "36") (pinfunction "P1[22]/MC0B/USB_PWRD/MAT1[0]_36") (pintype "bidirectional"))
      (node (ref "U1") (pin "A9") (pinfunction "A9_A9") (pintype "bidirectional"))
    )
    (net (code "63") (name "P1[23]") (class "Default")
      (node (ref "IC1") (pin "37") (pinfunction "P1[23]/MCFB1/PWM1[4]/MISO0_37") (pintype "bidirectional"))
      (node (ref "U1") (pin "A10") (pinfunction "A10_A10") (pintype "bidirectional"))
    )
    (net (code "64") (name "P1[24]") (class "Default")
      (node (ref "IC1") (pin "38") (pinfunction "P1[24]/MCFB2/PWM1[5]/MOSI0_38") (pintype "bidirectional"))
      (node (ref "U1") (pin "A2") (pinfunction "A2_A2") (pintype "bidirectional"))
    )
    (net (code "65") (name "P1[25]") (class "Default")
      (node (ref "IC1") (pin "39") (pinfunction "P1[25]/MC1A/MAT1[1]_39") (pintype "bidirectional"))
      (node (ref "U1") (pin "A11") (pinfunction "A11_A11") (pintype "bidirectional"))
    )
    (net (code "66") (name "P1[26]") (class "Default")
      (node (ref "IC1") (pin "40") (pinfunction "P1[26]/MC1B/PWM1[6]/CAP0[0]_40") (pintype "bidirectional"))
      (node (ref "U1") (pin "A6") (pinfunction "A6_A6") (pintype "bidirectional"))
    )
    (net (code "67") (name "P1[27]") (class "Default")
      (node (ref "IC1") (pin "43") (pinfunction "P1[27]/CLKOUT/USB_OVRCR/CAP0[1]_43") (pintype "bidirectional"))
      (node (ref "U1") (pin "A7") (pinfunction "A7_A7") (pintype "bidirectional"))
    )
    (net (code "68") (name "P1[28]") (class "Default")
      (node (ref "IC1") (pin "44") (pinfunction "P1[28]/MC2A/PCAP1[0]/MAT0[0]_44") (pintype "bidirectional"))
      (node (ref "U1") (pin "11") (pinfunction "11_11") (pintype "bidirectional"))
      (node (ref "U1") (pin "25") (pinfunction "25_25") (pintype "bidirectional"))
    )
    (net (code "69") (name "P1[29]") (class "Default")
      (node (ref "IC1") (pin "45") (pinfunction "P1[29]/MC2B/PCAP1[1]/MAT0[1]_45") (pintype "bidirectional"))
      (node (ref "U1") (pin "27") (pinfunction "27_27") (pintype "bidirectional"))
    )
    (net (code "70") (name "P1[30]") (class "Default")
      (node (ref "IC1") (pin "21") (pinfunction "P1[30]/VBUS/AD0[4]_21") (pintype "bidirectional"))
      (node (ref "U1") (pin "A14") (pinfunction "A14_A14") (pintype "bidirectional"))
    )
    (net (code "71") (name "P1[31]") (class "Default")
      (node (ref "IC1") (pin "20") (pinfunction "P1[31]/SCK1/AD0[5]_20") (pintype "bidirectional"))
      (node (ref "U1") (pin "A15") (pinfunction "A15_A15") (pintype "bidirectional"))
    )
    (net (code "72") (name "P2[0]") (class "Default")
      (node (ref "IC1") (pin "75") (pinfunction "P2[0]/PWM1[1]/TXD1_75") (pintype "bidirectional"))
      (node (ref "U1") (pin "6") (pinfunction "6_6") (pintype "bidirectional"))
    )
    (net (code "73") (name "P2[1]") (class "Default")
      (node (ref "IC1") (pin "74") (pinfunction "P2[1]/PWM1[2]/RXD1_74") (pintype "bidirectional"))
      (node (ref "U1") (pin "3") (pinfunction "3_3") (pintype "bidirectional"))
      (node (ref "U1") (pin "5") (pinfunction "5_5") (pintype "bidirectional"))
    )
    (net (code "74") (name "P2[2]") (class "Default")
      (node (ref "IC1") (pin "73") (pinfunction "P2[2]/PWM1[3]/CTS1/TRACEDATA[3]_73") (pintype "bidirectional"))
      (node (ref "U1") (pin "4") (pinfunction "4_4") (pintype "bidirectional"))
    )
    (net (code "75") (name "P2[3]") (class "Default")
      (node (ref "IC1") (pin "70") (pinfunction "P2[3]/PWM1[4]/DCD1/TRACEDATA[2]_70") (pintype "bidirectional"))
      (node (ref "U1") (pin "2") (pinfunction "2_2") (pintype "bidirectional"))
    )
    (net (code "76") (name "P2[4]") (class "Default")
      (node (ref "IC1") (pin "69") (pinfunction "P2[4]/PWM1[5]/DSR1/TRACEDATA[1]_69") (pintype "bidirectional"))
      (node (ref "U1") (pin "13") (pinfunction "13_13") (pintype "bidirectional"))
    )
    (net (code "77") (name "P2[5]") (class "Default")
      (node (ref "IC1") (pin "68") (pinfunction "P2[5]/PWM1[6]/DTR1/TRACEDATA[0]_68") (pintype "bidirectional"))
      (node (ref "U1") (pin "14") (pinfunction "14(TX3)_14") (pintype "bidirectional"))
    )
    (net (code "78") (name "P2[6]") (class "Default")
      (node (ref "IC1") (pin "67") (pinfunction "P2[6]/PCAP1[0]/RI1/TRACECLK_67") (pintype "bidirectional"))
      (node (ref "U1") (pin "15") (pinfunction "15(RX3)_15") (pintype "bidirectional"))
    )
    (net (code "79") (name "P2[7]") (class "Default")
      (node (ref "IC1") (pin "66") (pinfunction "P2[7]/RD2/RTS1_66") (pintype "bidirectional"))
      (node (ref "U1") (pin "18") (pinfunction "18(TX1)_18") (pintype "bidirectional"))
    )
    (net (code "80") (name "P2[8]") (class "Default")
      (node (ref "IC1") (pin "65") (pinfunction "P2[8]/TD2/TXD2_65") (pintype "bidirectional"))
      (node (ref "U1") (pin "19") (pinfunction "19(RX1)_19") (pintype "bidirectional"))
    )
    (net (code "81") (name "P2[10]") (class "Default")
      (node (ref "IC1") (pin "53") (pinfunction "P2[10]/EINT0/NMI_53") (pintype "bidirectional"))
      (node (ref "ISP") (pin "3") (pinfunction "I_3") (pintype "passive"))
      (node (ref "ISP") (pin "4") (pinfunction "I_4") (pintype "passive"))
      (node (ref "R5") (pin "1") (pinfunction "1_1") (pintype "passive"))
      (node (ref "U1") (pin "47") (pinfunction "47_47") (pintype "bidirectional"))
    )
    (net (code "82") (name "P2[11]") (class "Default")
      (node (ref "IC1") (pin "52") (pinfunction "P2[11]/EINT1/I2STX_CLK_52") (pintype "bidirectional"))
      (node (ref "U1") (pin "30") (pinfunction "30_30") (pintype "bidirectional"))
    )
    (net (code "83") (name "P2[12]") (class "Default")
      (node (ref "DFU") (pin "3") (pinfunction "I_3") (pintype "passive"))
      (node (ref "DFU") (pin "4") (pinfunction "I_4") (pintype "passive"))
      (node (ref "IC1") (pin "51") (pinfunction "P2[12]/EINT2/I2STX_WS_51") (pintype "bidirectional"))
      (node (ref "U1") (pin "34") (pinfunction "34_34") (pintype "bidirectional"))
      (node (ref "U1") (pin "40") (pinfunction "40_40") (pintype "bidirectional"))
    )
    (net (code "84") (name "P2[13]") (class "Default")
      (node (ref "IC1") (pin "50") (pinfunction "P2[13]/EINT3/I2STX_SDA_50") (pintype "bidirectional"))
      (node (ref "U1") (pin "36") (pinfunction "36_36") (pintype "bidirectional"))
    )
    (net (code "85") (name "P3[25]") (class "Default")
      (node (ref "IC1") (pin "27") (pinfunction "P3[25]/MAT0[0]/PWM1[2]_27") (pintype "bidirectional"))
      (node (ref "U1") (pin "A3") (pinfunction "A3_A3") (pintype "bidirectional"))
    )
    (net (code "86") (name "P3[26]") (class "Default")
      (node (ref "IC1") (pin "26") (pinfunction "P3[26]/STCLK/MAT0[1]/PWM1[3]_26") (pintype "bidirectional"))
      (node (ref "U1") (pin "A0") (pinfunction "A0(RX0)_A0") (pintype "bidirectional"))
    )
    (net (code "87") (name "P4[28]") (class "Default")
      (node (ref "IC1") (pin "82") (pinfunction "P4[28]/RX_MCLK/MAT2[0]/TXD3_82") (pintype "bidirectional"))
      (node (ref "U1") (pin "9") (pinfunction "9_9") (pintype "bidirectional"))
    )
    (net (code "88") (name "P4[29]") (class "Default")
      (node (ref "IC1") (pin "85") (pinfunction "P4[29]/TX_MCLK/MAT2[1]/RXD3_85") (pintype "bidirectional"))
      (node (ref "U1") (pin "12") (pinfunction "12_12") (pintype "bidirectional"))
    )
    (net (code "89") (name "RD+") (class "Default")
      (node (ref "C56") (pin "1") (pinfunction "1_1") (pintype "passive"))
      (node (ref "IC8") (pin "23") (pinfunction "RX+_23") (pintype "bidirectional"))
      (node (ref "R56") (pin "2") (pinfunction "2_2") (pintype "passive"))
      (node (ref "RJ1") (pin "RD+") (pinfunction "RD+_RD+") (pintype "bidirectional"))
    )
    (net (code "90") (name "RD-") (class "Default")
      (node (ref "C57") (pin "1") (pinfunction "1_1") (pintype "passive"))
      (node (ref "IC8") (pin "22") (pinfunction "RX-_22") (pintype "bidirectional"))
      (node (ref "R57") (pin "2") (pinfunction "2_2") (pintype "passive"))
      (node (ref "RJ1") (pin "RD-") (pinfunction "RD-_RD-") (pintype "bidirectional"))
    )
    (net (code "91") (name "RTCK") (class "Default")
      (node (ref "IC1") (pin "100") (pinfunction "RTCK_100") (pintype "bidirectional"))
      (node (ref "JTAG") (pin "7") (pinfunction "7_7") (pintype "passive"))
    )
    (net (code "92") (name "RX_0") (class "Default")
      (node (ref "FTDI") (pin "4") (pinfunction "4_4") (pintype "passive"))
      (node (ref "IC1") (pin "99") (pinfunction "P0[3]/RXD0/AD0[6]_99") (pintype "bidirectional"))
      (node (ref "U1") (pin "0") (pinfunction "0(RX0)_0") (pintype "bidirectional"))
    )
    (net (code "93") (name "SCL") (class "Default")
      (node (ref "IC1") (pin "24") (pinfunction "P0[28]/SCL0/USB_SCL_24") (pintype "bidirectional"))
      (node (ref "U1") (pin "21") (pinfunction "21(SCL)_21") (pintype "bidirectional"))
      (node (ref "U1") (pin "SCL1") (pinfunction "SCL_SCL1") (pintype "bidirectional"))
    )
    (net (code "94") (name "SDA") (class "Default")
      (node (ref "IC1") (pin "25") (pinfunction "P0[27]/SDA0/USB_SDA_25") (pintype "bidirectional"))
      (node (ref "U1") (pin "20") (pinfunction "20(SDA)_20") (pintype "bidirectional"))
      (node (ref "U1") (pin "SDA1") (pinfunction "SDA_SDA1") (pintype "bidirectional"))
    )
    (net (code "95") (name "SD_CS") (class "Default")
      (node (ref "IC1") (pin "79") (pinfunction "P0[6]/I2SRX_SDA/SSEL1/MAT2[0]_79") (pintype "bidirectional"))
      (node (ref "X1") (pin "2") (pinfunction "D3_2") (pintype "bidirectional"))
    )
    (net (code "96") (name "SD_MISO") (class "Default")
      (node (ref "IC1") (pin "77") (pinfunction "P0[8]/I2STX_WS/MISO1/MAT2[2]_77") (pintype "bidirectional"))
      (node (ref "U1") (pin "MISO") (pinfunction "MISO_MISO") (pintype "bidirectional"))
      (node (ref "X1") (pin "7") (pinfunction "D0_7") (pintype "bidirectional"))
    )
    (net (code "97") (name "SD_MOSI") (class "Default")
      (node (ref "IC1") (pin "76") (pinfunction "P0[9]/I2STX_SDA/MOSI1/MAT2[3]_76") (pintype "bidirectional"))
      (node (ref "U1") (pin "MOSI") (pinfunction "MOSI_MOSI") (pintype "bidirectional"))
      (node (ref "X1") (pin "3") (pinfunction "CMD_3") (pintype "bidirectional"))
    )
    (net (code "98") (name "SD_SCK") (class "Default")
      (node (ref "IC1") (pin "78") (pinfunction "P0[7]/I2STX_CLK/SCK1/MAT2[1]_78") (pintype "bidirectional"))
      (node (ref "U1") (pin "SCK") (pinfunction "SCK_SCK") (pintype "bidirectional"))
      (node (ref "X1") (pin "5") (pinfunction "CLK_5") (pintype "input"))
    )
    (net (code "99") (name "TCK-SWDCLK") (class "Default")
      (node (ref "IC1") (pin "5") (pinfunction "TCK/SWDCLK_5") (pintype "bidirectional"))
      (node (ref "JTAG") (pin "4") (pinfunction "4_4") (pintype "passive"))
    )
    (net (code "100") (name "TD+") (class "Default")
      (node (ref "C54") (pin "1") (pinfunction "1_1") (pintype "passive"))
      (node (ref "IC8") (pin "21") (pinfunction "TX+_21") (pintype "bidirectional"))
      (node (ref "R54") (pin "2") (pinfunction "2_2") (pintype "passive"))
      (node (ref "RJ1") (pin "TD+") (pinfunction "TD+_TD+") (pintype "bidirectional"))
    )
    (net (code "101") (name "TD-") (class "Default")
      (node (ref "C55") (pin "1") (pinfunction "1_1") (pintype "passive"))
      (node (ref "IC8") (pin "20") (pinfunction "TX-_20") (pintype "bidirectional"))
      (node (ref "R55") (pin "2") (pinfunction "2_2") (pintype "passive"))
      (node (ref "RJ1") (pin "TD-") (pinfunction "TD-_TD-") (pintype "bidirectional"))
    )
    (net (code "102") (name "TDI") (class "Default")
      (node (ref "IC1") (pin "2") (pinfunction "TDI_2") (pintype "bidirectional"))
      (node (ref "JTAG") (pin "8") (pinfunction "8_8") (pintype "passive"))
    )
    (net (code "103") (name "TDO-SWO") (class "Default")
      (node (ref "IC1") (pin "1") (pinfunction "TDO/SWO_1") (pintype "bidirectional"))
      (node (ref "JTAG") (pin "6") (pinfunction "6_6") (pintype "passive"))
    )
    (net (code "104") (name "TMS-SWDIO") (class "Default")
      (node (ref "IC1") (pin "3") (pinfunction "TMS/SWDIO_3") (pintype "bidirectional"))
      (node (ref "JTAG") (pin "2") (pinfunction "2_2") (pintype "passive"))
    )
    (net (code "105") (name "TX_0") (class "Default")
      (node (ref "FTDI") (pin "5") (pinfunction "5_5") (pintype "passive"))
      (node (ref "IC1") (pin "98") (pinfunction "P0[2]/TXD0/AD0[7]_98") (pintype "bidirectional"))
      (node (ref "U1") (pin "1") (pinfunction "1(TX0)_1") (pintype "bidirectional"))
    )
    (net (code "106") (name "USB_CONNECT") (class "Default")
      (node (ref "IC1") (pin "64") (pinfunction "P2[9]/USB_CONNECT/RXD2_64") (pintype "bidirectional"))
      (node (ref "Q1") (pin "3") (pinfunction "G_3") (pintype "passive"))
    )
    (net (code "107") (name "USB_N") (class "Default")
      (node (ref "C4") (pin "2") (pinfunction "2_2") (pintype "passive"))
      (node (ref "IC1") (pin "30") (pinfunction "P0[30]/USB_D-_30") (pintype "bidirectional"))
      (node (ref "R9") (pin "2") (pinfunction "2_2") (pintype "passive"))
    )
    (net (code "108") (name "USB_P") (class "Default")
      (node (ref "C5") (pin "2") (pinfunction "2_2") (pintype "passive"))
      (node (ref "IC1") (pin "29") (pinfunction "P0[29]/USB_D+_29") (pintype "bidirectional"))
      (node (ref "R7") (pin "1") (pinfunction "1_1") (pintype "passive"))
      (node (ref "R8") (pin "2") (pinfunction "2_2") (pintype "passive"))
    )
    (net (code "109") (name "VUSB") (class "Default")
      (node (ref "D1") (pin "A") (pinfunction "A_A") (pintype "passive"))
      (node (ref "PTC1") (pin "1") (pinfunction "1_1") (pintype "passive"))
    )
    (net (code "110") (name "unconnected-(FTDI-Pad2)") (class "Default")
      (node (ref "FTDI") (pin "2") (pinfunction "2_2") (pintype "passive"))
    )
    (net (code "111") (name "unconnected-(FTDI-Pad3)") (class "Default")
      (node (ref "FTDI") (pin "3") (pinfunction "3_3") (pintype "passive"))
    )
    (net (code "112") (name "unconnected-(FTDI-Pad6)") (class "Default")
      (node (ref "FTDI") (pin "6") (pinfunction "6_6") (pintype "passive"))
    )
    (net (code "113") (name "unconnected-(IC1-RTCX1-Pad16)") (class "Default")
      (node (ref "IC1") (pin "16") (pinfunction "RTCX1_16") (pintype "bidirectional"))
    )
    (net (code "114") (name "unconnected-(IC1-RTCX2-Pad18)") (class "Default")
      (node (ref "IC1") (pin "18") (pinfunction "RTCX2_18") (pintype "bidirectional"))
    )
    (net (code "115") (name "unconnected-(IC1-TRST-Pad4)") (class "Default")
      (node (ref "IC1") (pin "4") (pinfunction "TRST_4") (pintype "bidirectional"))
    )
    (net (code "116") (name "unconnected-(IC7-NC-Pad1)") (class "Default")
      (node (ref "IC7") (pin "1") (pinfunction "NC_1") (pintype "no_connect"))
    )
    (net (code "117") (name "unconnected-(RJ1-PadNC)") (class "Default")
      (node (ref "RJ1") (pin "NC") (pinfunction "NC_NC") (pintype "bidirectional"))
    )
    (net (code "118") (name "unconnected-(U1-16(TX2)-Pad16)") (class "Default")
      (node (ref "U1") (pin "16") (pinfunction "16(TX2)_16") (pintype "bidirectional"))
    )
    (net (code "119") (name "unconnected-(U1-17(RX2)-Pad17)") (class "Default")
      (node (ref "U1") (pin "17") (pinfunction "17(RX2)_17") (pintype "bidirectional"))
    )
    (net (code "120") (name "unconnected-(U1-Pad29)") (class "Default")
      (node (ref "U1") (pin "29") (pinfunction "29_29") (pintype "bidirectional"))
    )
    (net (code "121") (name "unconnected-(U1-Pad31)") (class "Default")
      (node (ref "U1") (pin "31") (pinfunction "31_31") (pintype "bidirectional"))
    )
    (net (code "122") (name "unconnected-(U1-Pad33)") (class "Default")
      (node (ref "U1") (pin "33") (pinfunction "33_33") (pintype "bidirectional"))
    )
    (net (code "123") (name "unconnected-(U1-Pad35)") (class "Default")
      (node (ref "U1") (pin "35") (pinfunction "35_35") (pintype "bidirectional"))
    )
    (net (code "124") (name "unconnected-(U1-Pad37)") (class "Default")
      (node (ref "U1") (pin "37") (pinfunction "37_37") (pintype "bidirectional"))
    )
    (net (code "125") (name "unconnected-(U1-Pad39)") (class "Default")
      (node (ref "U1") (pin "39") (pinfunction "39_39") (pintype "bidirectional"))
    )
    (net (code "126") (name "unconnected-(U1-Pad41)") (class "Default")
      (node (ref "U1") (pin "41") (pinfunction "41_41") (pintype "bidirectional"))
    )
    (net (code "127") (name "unconnected-(U1-Pad43)") (class "Default")
      (node (ref "U1") (pin "43") (pinfunction "43_43") (pintype "bidirectional"))
    )
    (net (code "128") (name "unconnected-(U1-Pad45)") (class "Default")
      (node (ref "U1") (pin "45") (pinfunction "45_45") (pintype "bidirectional"))
    )
    (net (code "129") (name "unconnected-(U1-Pad53)") (class "Default")
      (node (ref "U1") (pin "53") (pinfunction "53_53") (pintype "bidirectional"))
    )
    (net (code "130") (name "unconnected-(U1-PadA4)") (class "Default")
      (node (ref "U1") (pin "A4") (pinfunction "A4_A4") (pintype "bidirectional"))
    )
    (net (code "131") (name "unconnected-(U1-PadA5)") (class "Default")
      (node (ref "U1") (pin "A5") (pinfunction "A5_A5") (pintype "bidirectional"))
    )
    (net (code "132") (name "unconnected-(U1-PadAREF)") (class "Default")
      (node (ref "U1") (pin "AREF") (pinfunction "AREF_AREF") (pintype "bidirectional"))
    )
    (net (code "133") (name "unconnected-(U1-PadVIN)") (class "Default")
      (node (ref "U1") (pin "VIN") (pinfunction "VIN_VIN") (pintype "bidirectional"))
    )
    (net (code "134") (name "unconnected-(X1-D1-Pad8)") (class "Default")
      (node (ref "X1") (pin "8") (pinfunction "D1_8") (pintype "bidirectional"))
    )
    (net (code "135") (name "unconnected-(X1-D2-Pad1)") (class "Default")
      (node (ref "X1") (pin "1") (pinfunction "D2_1") (pintype "bidirectional"))
    )
    (net (code "136") (name "unconnected-(X2-ID-Pad4)") (class "Default")
      (node (ref "X2") (pin "4") (pinfunction "ID_4") (pintype "bidirectional"))
    )
    (net (code "137") (name "~{RSTOUT}") (class "Default")
      (node (ref "IC1") (pin "14") (pinfunction "RSTOUT_14") (pintype "bidirectional"))
      (node (ref "IC8") (pin "15") (pinfunction "NRST_15") (pintype "bidirectional"))
    )
    (net (code "138") (name "~{RST}") (class "Default")
      (node (ref "IC1") (pin "17") (pinfunction "RESET_17") (pintype "bidirectional"))
      (node (ref "JTAG") (pin "10") (pinfunction "10_10") (pintype "passive"))
      (node (ref "R4") (pin "1") (pinfunction "1_1") (pintype "passive"))
      (node (ref "RST") (pin "3") (pinfunction "I_3") (pintype "passive"))
      (node (ref "RST") (pin "4") (pinfunction "I_4") (pintype "passive"))
      (node (ref "U1") (pin "RESET") (pinfunction "RESET_RESET") (pintype "bidirectional"))
      (node (ref "U1") (pin "RST") (pinfunction "RESET_RST") (pintype "bidirectional"))
    )
  )
)
